# BOOT_SET.net
KiCad netlist of a schematic drawn in Altium Designer
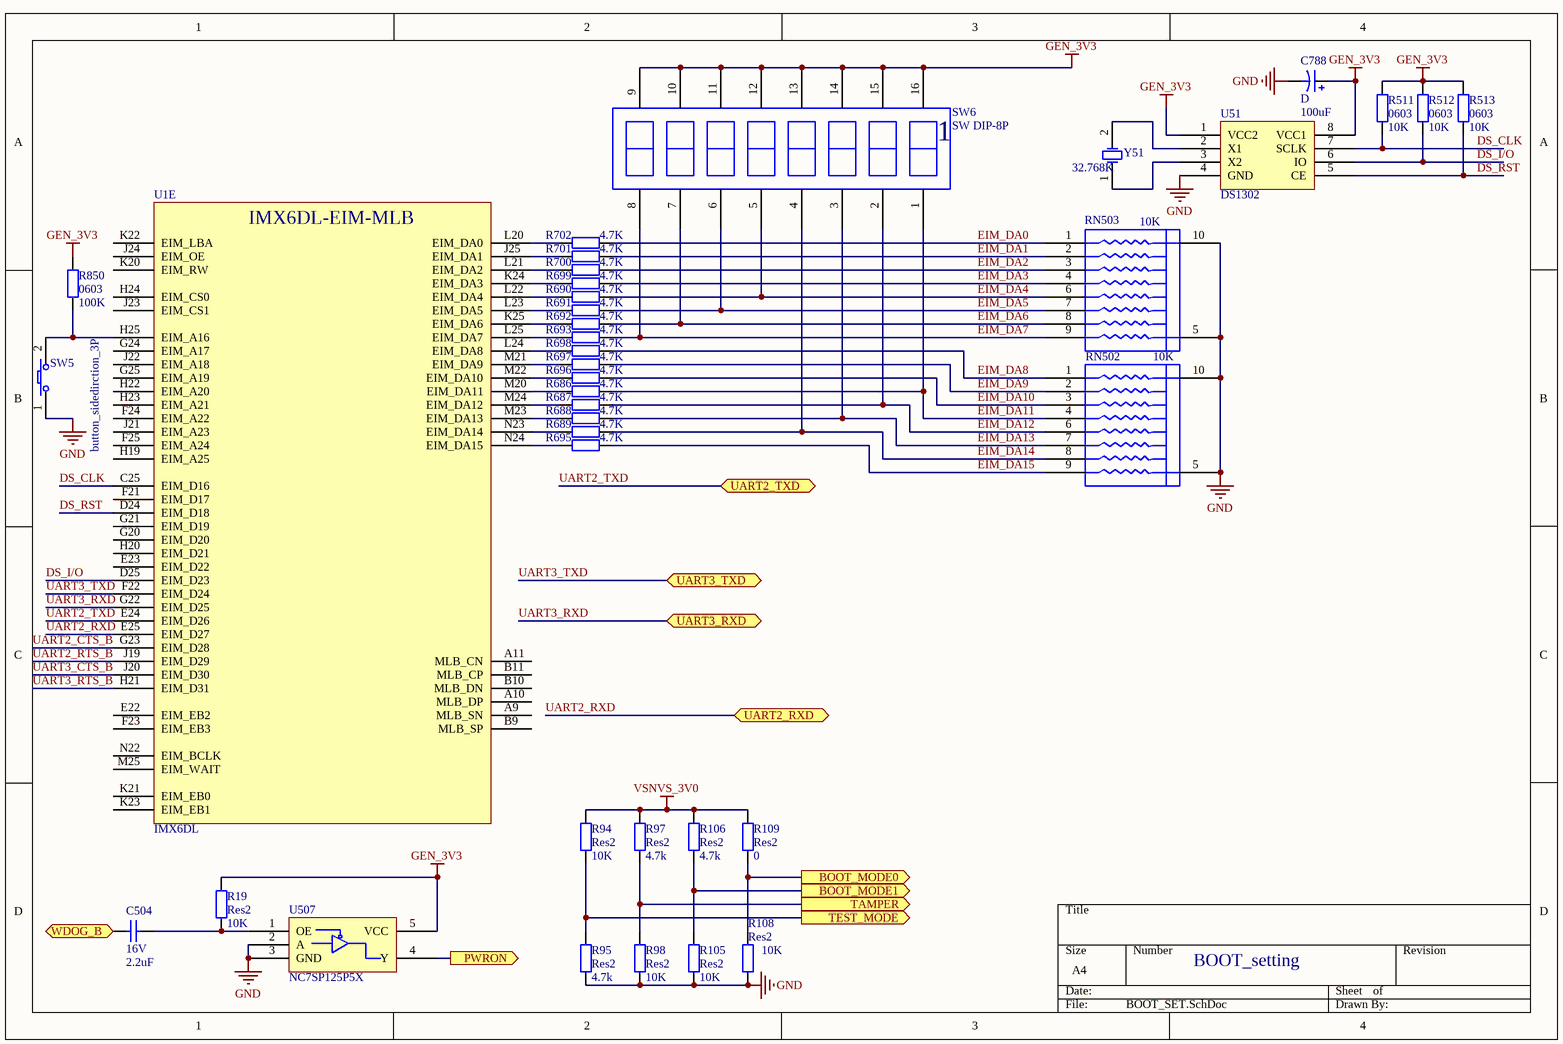
[diagram p0: BOOT_SET.SchDoc]

(export (version "E")
  (design (tool "Eeschema 10.0.6"))
  (components
    (comp (ref "C504")
      (value "16V")
      (footprint "0603")
      (description "Capacitor")
      (fields (field (name "ALTIUM_VALUE") "2.2uF") (field (name "PUBLISHER") "Altium Limited"))
      (libsource (lib "Miscellaneous Devices") (part "Cap"))
    )
    (comp (ref "C788")
      (value "D")
      (footprint "D")
      (description "Polarized Capacitor (Radial)")
      (fields (field (name "ALTIUM_VALUE") "100uF") (field (name "PUBLISHER") "Altium Limited"))
      (libsource (lib "Miscellaneous Devices") (part "Cap Pol1"))
    )
    (comp (ref "R19")
      (value "Res2")
      (footprint "0402")
      (description "Resistor")
      (fields (field (name "ALTIUM_VALUE") "10K") (field (name "PUBLISHER") "Altium Limited"))
      (libsource (lib "") (part "Res2_1"))
    )
    (comp (ref "R94")
      (value "Res2")
      (footprint "0402")
      (description "Resistor")
      (fields (field (name "ALTIUM_VALUE") "10K") (field (name "PUBLISHER") "Altium Limited"))
      (libsource (lib "") (part "Res2_1"))
    )
    (comp (ref "R95")
      (value "Res2")
      (footprint "0402")
      (description "Resistor")
      (fields (field (name "ALTIUM_VALUE") "4.7k") (field (name "PUBLISHER") "Altium Limited"))
      (libsource (lib "") (part "Res2_1"))
    )
    (comp (ref "R97")
      (value "Res2")
      (footprint "0402")
      (description "Resistor")
      (fields (field (name "ALTIUM_VALUE") "4.7k") (field (name "PUBLISHER") "Altium Limited"))
      (libsource (lib "") (part "Res2_1"))
    )
    (comp (ref "R98")
      (value "Res2")
      (footprint "0402")
      (description "Resistor")
      (fields (field (name "ALTIUM_VALUE") "10K") (field (name "PUBLISHER") "Altium Limited"))
      (libsource (lib "") (part "Res2_1"))
    )
    (comp (ref "R105")
      (value "Res2")
      (footprint "0402")
      (description "Resistor")
      (fields (field (name "ALTIUM_VALUE") "10K") (field (name "PUBLISHER") "Altium Limited"))
      (libsource (lib "") (part "Res2_1"))
    )
    (comp (ref "R106")
      (value "Res2")
      (footprint "0402")
      (description "Resistor")
      (fields (field (name "ALTIUM_VALUE") "4.7k") (field (name "PUBLISHER") "Altium Limited"))
      (libsource (lib "") (part "Res2_1"))
    )
    (comp (ref "R108")
      (value "Res2")
      (footprint "0402")
      (description "Resistor")
      (fields (field (name "ALTIUM_VALUE") "10K") (field (name "PUBLISHER") "Altium Limited"))
      (libsource (lib "") (part "Res2_1"))
    )
    (comp (ref "R109")
      (value "Res2")
      (footprint "0402")
      (description "Resistor")
      (fields (field (name "ALTIUM_VALUE") "0") (field (name "PUBLISHER") "Altium Limited"))
      (libsource (lib "") (part "Res2_1"))
    )
    (comp (ref "R511")
      (value "0603")
      (footprint "0603")
      (description "Resistor")
      (fields (field (name "ALTIUM_VALUE") "10K") (field (name "PUBLISHER") "Altium Limited"))
      (libsource (lib "") (part "Res2_1"))
    )
    (comp (ref "R512")
      (value "0603")
      (footprint "0603")
      (description "Resistor")
      (fields (field (name "ALTIUM_VALUE") "10K") (field (name "PUBLISHER") "Altium Limited"))
      (libsource (lib "") (part "Res2_1"))
    )
    (comp (ref "R513")
      (value "0603")
      (footprint "0603")
      (description "Resistor")
      (fields (field (name "ALTIUM_VALUE") "10K") (field (name "PUBLISHER") "Altium Limited"))
      (libsource (lib "") (part "Res2_1"))
    )
    (comp (ref "R686")
      (value "4.7K")
      (footprint "0402")
      (description "Resistor")
      (fields (field (name "Comment") "Res2") (field (name "PUBLISHER") "Altium Limited"))
      (libsource (lib "Miscellaneous Devices") (part "Res2"))
    )
    (comp (ref "R687")
      (value "4.7K")
      (footprint "0402")
      (description "Resistor")
      (fields (field (name "Comment") "Res2") (field (name "PUBLISHER") "Altium Limited"))
      (libsource (lib "Miscellaneous Devices") (part "Res2"))
    )
    (comp (ref "R688")
      (value "4.7K")
      (footprint "0402")
      (description "Resistor")
      (fields (field (name "Comment") "Res2") (field (name "PUBLISHER") "Altium Limited"))
      (libsource (lib "Miscellaneous Devices") (part "Res2"))
    )
    (comp (ref "R689")
      (value "4.7K")
      (footprint "0402")
      (description "Resistor")
      (fields (field (name "Comment") "Res2") (field (name "PUBLISHER") "Altium Limited"))
      (libsource (lib "Miscellaneous Devices") (part "Res2"))
    )
    (comp (ref "R690")
      (value "4.7K")
      (footprint "0402")
      (description "Resistor")
      (fields (field (name "Comment") "Res2") (field (name "PUBLISHER") "Altium Limited"))
      (libsource (lib "Miscellaneous Devices") (part "Res2"))
    )
    (comp (ref "R691")
      (value "4.7K")
      (footprint "0402")
      (description "Resistor")
      (fields (field (name "Comment") "Res2") (field (name "PUBLISHER") "Altium Limited"))
      (libsource (lib "Miscellaneous Devices") (part "Res2"))
    )
    (comp (ref "R692")
      (value "4.7K")
      (footprint "0402")
      (description "Resistor")
      (fields (field (name "Comment") "Res2") (field (name "PUBLISHER") "Altium Limited"))
      (libsource (lib "Miscellaneous Devices") (part "Res2"))
    )
    (comp (ref "R693")
      (value "4.7K")
      (footprint "0402")
      (description "Resistor")
      (fields (field (name "Comment") "Res2") (field (name "PUBLISHER") "Altium Limited"))
      (libsource (lib "Miscellaneous Devices") (part "Res2"))
    )
    (comp (ref "R695")
      (value "4.7K")
      (footprint "0402")
      (description "Resistor")
      (fields (field (name "Comment") "Res2") (field (name "PUBLISHER") "Altium Limited"))
      (libsource (lib "Miscellaneous Devices") (part "Res2"))
    )
    (comp (ref "R696")
      (value "4.7K")
      (footprint "0402")
      (description "Resistor")
      (fields (field (name "Comment") "Res2") (field (name "PUBLISHER") "Altium Limited"))
      (libsource (lib "Miscellaneous Devices") (part "Res2"))
    )
    (comp (ref "R697")
      (value "4.7K")
      (footprint "0402")
      (description "Resistor")
      (fields (field (name "Comment") "Res2") (field (name "PUBLISHER") "Altium Limited"))
      (libsource (lib "Miscellaneous Devices") (part "Res2"))
    )
    (comp (ref "R698")
      (value "4.7K")
      (footprint "0402")
      (description "Resistor")
      (fields (field (name "Comment") "Res2") (field (name "PUBLISHER") "Altium Limited"))
      (libsource (lib "Miscellaneous Devices") (part "Res2"))
    )
    (comp (ref "R699")
      (value "4.7K")
      (footprint "0402")
      (description "Resistor")
      (fields (field (name "Comment") "Res2") (field (name "PUBLISHER") "Altium Limited"))
      (libsource (lib "Miscellaneous Devices") (part "Res2"))
    )
    (comp (ref "R700")
      (value "4.7K")
      (footprint "0402")
      (description "Resistor")
      (fields (field (name "Comment") "Res2") (field (name "PUBLISHER") "Altium Limited"))
      (libsource (lib "Miscellaneous Devices") (part "Res2"))
    )
    (comp (ref "R701")
      (value "4.7K")
      (footprint "0402")
      (description "Resistor")
      (fields (field (name "Comment") "Res2") (field (name "PUBLISHER") "Altium Limited"))
      (libsource (lib "Miscellaneous Devices") (part "Res2"))
    )
    (comp (ref "R702")
      (value "4.7K")
      (footprint "0402")
      (description "Resistor")
      (fields (field (name "Comment") "Res2") (field (name "PUBLISHER") "Altium Limited"))
      (libsource (lib "Miscellaneous Devices") (part "Res2"))
    )
    (comp (ref "R850")
      (value "0603")
      (footprint "0603")
      (description "Resistor")
      (fields (field (name "ALTIUM_VALUE") "100K") (field (name "PUBLISHER") "Altium Limited"))
      (libsource (lib "") (part "Res2_1"))
    )
    (comp (ref "RN502")
      (value "10K")
      (footprint "RN_resistance -SMT8")
      (libsource (lib "IMX6DL") (part "RN res"))
    )
    (comp (ref "RN503")
      (value "10K")
      (footprint "RN_resistance -SMT8")
      (libsource (lib "IMX6DL") (part "RN res"))
    )
    (comp (ref "SW5")
      (value "button_sidedirction_3P")
      (footprint "button_sidedirction_3P 4.5X4.5")
      (libsource (lib "IMX6DL") (part "button_sidedirction_3P"))
    )
    (comp (ref "SW6")
      (value "SW DIP-8P")
      (footprint "dial switch -SMT DIP8")
      (libsource (lib "IMX6DL") (part "SW-8P"))
    )
    (comp (ref "U1")
      (value "IMX6DL")
      (footprint "IMX6DL-BGA624x25")
      (libsource (lib "IMX6DL") (part "IMX6DL"))
    )
    (comp (ref "U51") (value "DS1302") (footprint "DS1302-DIP8") (libsource (lib "IMX6DL") (part "DS1302")))
    (comp (ref "U507")
      (value "NC7SP125P5X")
      (footprint "NC7SP125P5X")
      (libsource (lib "IMX6DL") (part "NC7SP125P5X"))
    )
    (comp (ref "Y51")
      (value "32.768K")
      (footprint "BCY-W2/D3.1")
      (description "Crystal Oscillator")
      (fields (field (name "PUBLISHER") "Altium Limited"))
      (libsource (lib "Miscellaneous Devices") (part "XTAL"))
    )
  )
  (nets
    (net (code "1") (name "/BOOT_MODE0") (class "Default")
      (node (ref "R108") (pin "2") (pinfunction "2_2") (pintype "passive"))
      (node (ref "R109") (pin "1") (pinfunction "1_1") (pintype "passive"))
    )
    (net (code "2") (name "/BOOT_MODE1") (class "Default")
      (node (ref "R105") (pin "2") (pinfunction "2_2") (pintype "passive"))
      (node (ref "R106") (pin "1") (pinfunction "1_1") (pintype "passive"))
    )
    (net (code "3") (name "/DS_CLK") (class "Default")
      (node (ref "R511") (pin "1") (pinfunction "1_1") (pintype "passive"))
      (node (ref "U1") (pin "C25") (pinfunction "EIM_D16_C25") (pintype "passive"))
      (node (ref "U51") (pin "7") (pinfunction "SCLK_7") (pintype "passive"))
    )
    (net (code "4") (name "/DS_I{slash}O") (class "Default")
      (node (ref "R512") (pin "1") (pinfunction "1_1") (pintype "passive"))
      (node (ref "U1") (pin "D25") (pinfunction "EIM_D23_D25") (pintype "passive"))
      (node (ref "U51") (pin "6") (pinfunction "IO_6") (pintype "passive"))
    )
    (net (code "5") (name "/DS_RST") (class "Default")
      (node (ref "R513") (pin "1") (pinfunction "1_1") (pintype "passive"))
      (node (ref "U1") (pin "D24") (pinfunction "EIM_D18_D24") (pintype "passive"))
      (node (ref "U51") (pin "5") (pinfunction "CE_5") (pintype "passive"))
    )
    (net (code "6") (name "/EIM_DA0") (class "Default")
      (node (ref "R702") (pin "2") (pinfunction "2_2") (pintype "passive"))
      (node (ref "RN503") (pin "1") (pinfunction "19_1") (pintype "passive"))
    )
    (net (code "7") (name "/EIM_DA1") (class "Default")
      (node (ref "R701") (pin "2") (pinfunction "2_2") (pintype "passive"))
      (node (ref "RN503") (pin "2") (pinfunction "20_2") (pintype "passive"))
    )
    (net (code "8") (name "/EIM_DA2") (class "Default")
      (node (ref "R700") (pin "2") (pinfunction "2_2") (pintype "passive"))
      (node (ref "RN503") (pin "3") (pinfunction "21_3") (pintype "passive"))
    )
    (net (code "9") (name "/EIM_DA3") (class "Default")
      (node (ref "R699") (pin "2") (pinfunction "2_2") (pintype "passive"))
      (node (ref "RN503") (pin "4") (pinfunction "22_4") (pintype "passive"))
    )
    (net (code "10") (name "/EIM_DA4") (class "Default")
      (node (ref "R690") (pin "2") (pinfunction "2_2") (pintype "passive"))
      (node (ref "RN503") (pin "6") (pinfunction "23_6") (pintype "passive"))
      (node (ref "SW6") (pin "5") (pinfunction "VDDUSB_CAP_5") (pintype "passive"))
    )
    (net (code "11") (name "/EIM_DA5") (class "Default")
      (node (ref "R691") (pin "2") (pinfunction "2_2") (pintype "passive"))
      (node (ref "RN503") (pin "7") (pinfunction "24_7") (pintype "passive"))
      (node (ref "SW6") (pin "6") (pinfunction "VDDUSB_CAP_6") (pintype "passive"))
    )
    (net (code "12") (name "/EIM_DA6") (class "Default")
      (node (ref "R692") (pin "2") (pinfunction "2_2") (pintype "passive"))
      (node (ref "RN503") (pin "8") (pinfunction "25_8") (pintype "passive"))
      (node (ref "SW6") (pin "7") (pinfunction "VDDUSB_CAP_7") (pintype "passive"))
    )
    (net (code "13") (name "/EIM_DA7") (class "Default")
      (node (ref "R693") (pin "2") (pinfunction "2_2") (pintype "passive"))
      (node (ref "RN503") (pin "9") (pinfunction "26_9") (pintype "passive"))
      (node (ref "SW6") (pin "8") (pinfunction "VDDUSB_CAP_8") (pintype "passive"))
    )
    (net (code "14") (name "/EIM_DA8") (class "Default")
      (node (ref "R698") (pin "2") (pinfunction "2_2") (pintype "passive"))
      (node (ref "RN502") (pin "1") (pinfunction "19_1") (pintype "passive"))
    )
    (net (code "15") (name "/EIM_DA9") (class "Default")
      (node (ref "R697") (pin "2") (pinfunction "2_2") (pintype "passive"))
      (node (ref "RN502") (pin "2") (pinfunction "20_2") (pintype "passive"))
    )
    (net (code "16") (name "/EIM_DA10") (class "Default")
      (node (ref "R696") (pin "2") (pinfunction "2_2") (pintype "passive"))
      (node (ref "RN502") (pin "3") (pinfunction "21_3") (pintype "passive"))
    )
    (net (code "17") (name "/EIM_DA11") (class "Default")
      (node (ref "R686") (pin "2") (pinfunction "2_2") (pintype "passive"))
      (node (ref "RN502") (pin "4") (pinfunction "22_4") (pintype "passive"))
      (node (ref "SW6") (pin "1") (pinfunction "VDDUSB_CAP_1") (pintype "passive"))
    )
    (net (code "18") (name "/EIM_DA12") (class "Default")
      (node (ref "R687") (pin "2") (pinfunction "2_2") (pintype "passive"))
      (node (ref "RN502") (pin "6") (pinfunction "23_6") (pintype "passive"))
      (node (ref "SW6") (pin "2") (pinfunction "VDDUSB_CAP_2") (pintype "passive"))
    )
    (net (code "19") (name "/EIM_DA13") (class "Default")
      (node (ref "R688") (pin "2") (pinfunction "2_2") (pintype "passive"))
      (node (ref "RN502") (pin "7") (pinfunction "24_7") (pintype "passive"))
      (node (ref "SW6") (pin "3") (pinfunction "VDDUSB_CAP_3") (pintype "passive"))
    )
    (net (code "20") (name "/EIM_DA14") (class "Default")
      (node (ref "R689") (pin "2") (pinfunction "2_2") (pintype "passive"))
      (node (ref "RN502") (pin "8") (pinfunction "25_8") (pintype "passive"))
      (node (ref "SW6") (pin "4") (pinfunction "VDDUSB_CAP_4") (pintype "passive"))
    )
    (net (code "21") (name "/EIM_DA15") (class "Default")
      (node (ref "R695") (pin "2") (pinfunction "2_2") (pintype "passive"))
      (node (ref "RN502") (pin "9") (pinfunction "26_9") (pintype "passive"))
    )
    (net (code "22") (name "/PWRON") (class "Default")
      (node (ref "U507") (pin "4") (pinfunction "Y_4") (pintype "passive"))
    )
    (net (code "23") (name "/TAMPER") (class "Default")
      (node (ref "R97") (pin "1") (pinfunction "1_1") (pintype "passive"))
      (node (ref "R98") (pin "2") (pinfunction "2_2") (pintype "passive"))
    )
    (net (code "24") (name "/TEST_MODE") (class "Default")
      (node (ref "R94") (pin "1") (pinfunction "1_1") (pintype "passive"))
      (node (ref "R95") (pin "2") (pinfunction "2_2") (pintype "passive"))
    )
    (net (code "25") (name "/UART2_CTS_B") (class "Default")
      (node (ref "U1") (pin "G23") (pinfunction "EIM_D28_G23") (pintype "passive"))
    )
    (net (code "26") (name "/UART2_RTS_B") (class "Default")
      (node (ref "U1") (pin "J19") (pinfunction "EIM_D29_J19") (pintype "passive"))
    )
    (net (code "27") (name "/UART2_RXD") (class "Default")
      (node (ref "U1") (pin "E25") (pinfunction "EIM_D27_E25") (pintype "passive"))
    )
    (net (code "28") (name "/UART2_TXD") (class "Default")
      (node (ref "U1") (pin "E24") (pinfunction "EIM_D26_E24") (pintype "passive"))
    )
    (net (code "29") (name "/UART3_CTS_B") (class "Default")
      (node (ref "U1") (pin "J20") (pinfunction "EIM_D30_J20") (pintype "passive"))
    )
    (net (code "30") (name "/UART3_RTS_B") (class "Default")
      (node (ref "U1") (pin "H21") (pinfunction "EIM_D31_H21") (pintype "passive"))
    )
    (net (code "31") (name "/UART3_RXD") (class "Default")
      (node (ref "U1") (pin "G22") (pinfunction "EIM_D25_G22") (pintype "passive"))
    )
    (net (code "32") (name "/UART3_TXD") (class "Default")
      (node (ref "U1") (pin "F22") (pinfunction "EIM_D24_F22") (pintype "passive"))
    )
    (net (code "33") (name "/WDOG_B") (class "Default")
      (node (ref "C504") (pin "1") (pinfunction "1_1") (pintype "passive"))
    )
    (net (code "34") (name "GEN_3V3") (class "Default")
      (node (ref "C788") (pin "1") (pinfunction "1_1") (pintype "passive"))
      (node (ref "R19") (pin "2") (pinfunction "2_2") (pintype "passive"))
      (node (ref "R511") (pin "2") (pinfunction "2_2") (pintype "passive"))
      (node (ref "R512") (pin "2") (pinfunction "2_2") (pintype "passive"))
      (node (ref "R513") (pin "2") (pinfunction "2_2") (pintype "passive"))
      (node (ref "R850") (pin "2") (pinfunction "2_2") (pintype "passive"))
      (node (ref "SW6") (pin "10") (pinfunction "10_10") (pintype "passive"))
      (node (ref "SW6") (pin "11") (pinfunction "11_11") (pintype "passive"))
      (node (ref "SW6") (pin "12") (pinfunction "12_12") (pintype "passive"))
      (node (ref "SW6") (pin "13") (pinfunction "13_13") (pintype "passive"))
      (node (ref "SW6") (pin "14") (pinfunction "14_14") (pintype "passive"))
      (node (ref "SW6") (pin "15") (pinfunction "15_15") (pintype "passive"))
      (node (ref "SW6") (pin "16") (pinfunction "16_16") (pintype "passive"))
      (node (ref "SW6") (pin "9") (pinfunction "9_9") (pintype "passive"))
      (node (ref "U507") (pin "5") (pinfunction "VCC_5") (pintype "passive"))
      (node (ref "U51") (pin "1") (pinfunction "VCC2_1") (pintype "passive"))
      (node (ref "U51") (pin "8") (pinfunction "VCC1_8") (pintype "passive"))
    )
    (net (code "35") (name "GND") (class "Default")
      (node (ref "C788") (pin "2") (pinfunction "2_2") (pintype "passive"))
      (node (ref "R105") (pin "1") (pinfunction "1_1") (pintype "passive"))
      (node (ref "R108") (pin "1") (pinfunction "1_1") (pintype "passive"))
      (node (ref "R95") (pin "1") (pinfunction "1_1") (pintype "passive"))
      (node (ref "R98") (pin "1") (pinfunction "1_1") (pintype "passive"))
      (node (ref "RN502") (pin "10") (pinfunction "18_10") (pintype "passive"))
      (node (ref "RN502") (pin "5") (pinfunction "17_5") (pintype "passive"))
      (node (ref "RN503") (pin "10") (pinfunction "18_10") (pintype "passive"))
      (node (ref "RN503") (pin "5") (pinfunction "17_5") (pintype "passive"))
      (node (ref "SW5") (pin "1") (pinfunction "3_1") (pintype "passive"))
      (node (ref "U507") (pin "2") (pinfunction "A_2") (pintype "passive"))
      (node (ref "U507") (pin "3") (pinfunction "GND_3") (pintype "passive"))
      (node (ref "U51") (pin "4") (pinfunction "GND_4") (pintype "passive"))
    )
    (net (code "36") (name "Net-(U1E-EIM_A16)") (class "Default")
      (node (ref "R850") (pin "1") (pinfunction "1_1") (pintype "passive"))
      (node (ref "SW5") (pin "2") (pinfunction "2_2") (pintype "passive"))
      (node (ref "U1") (pin "H25") (pinfunction "EIM_A16_H25") (pintype "passive"))
    )
    (net (code "37") (name "Net-(U1E-EIM_DA0)") (class "Default")
      (node (ref "R702") (pin "1") (pinfunction "1_1") (pintype "passive"))
      (node (ref "U1") (pin "L20") (pinfunction "EIM_DA0_L20") (pintype "passive"))
    )
    (net (code "38") (name "Net-(U1E-EIM_DA1)") (class "Default")
      (node (ref "R701") (pin "1") (pinfunction "1_1") (pintype "passive"))
      (node (ref "U1") (pin "J25") (pinfunction "EIM_DA1_J25") (pintype "passive"))
    )
    (net (code "39") (name "Net-(U1E-EIM_DA2)") (class "Default")
      (node (ref "R700") (pin "1") (pinfunction "1_1") (pintype "passive"))
      (node (ref "U1") (pin "L21") (pinfunction "EIM_DA2_L21") (pintype "passive"))
    )
    (net (code "40") (name "Net-(U1E-EIM_DA3)") (class "Default")
      (node (ref "R699") (pin "1") (pinfunction "1_1") (pintype "passive"))
      (node (ref "U1") (pin "K24") (pinfunction "EIM_DA3_K24") (pintype "passive"))
    )
    (net (code "41") (name "Net-(U1E-EIM_DA4)") (class "Default")
      (node (ref "R690") (pin "1") (pinfunction "1_1") (pintype "passive"))
      (node (ref "U1") (pin "L22") (pinfunction "EIM_DA4_L22") (pintype "passive"))
    )
    (net (code "42") (name "Net-(U1E-EIM_DA5)") (class "Default")
      (node (ref "R691") (pin "1") (pinfunction "1_1") (pintype "passive"))
      (node (ref "U1") (pin "L23") (pinfunction "EIM_DA5_L23") (pintype "passive"))
    )
    (net (code "43") (name "Net-(U1E-EIM_DA6)") (class "Default")
      (node (ref "R692") (pin "1") (pinfunction "1_1") (pintype "passive"))
      (node (ref "U1") (pin "K25") (pinfunction "EIM_DA6_K25") (pintype "passive"))
    )
    (net (code "44") (name "Net-(U1E-EIM_DA7)") (class "Default")
      (node (ref "R693") (pin "1") (pinfunction "1_1") (pintype "passive"))
      (node (ref "U1") (pin "L25") (pinfunction "EIM_DA7_L25") (pintype "passive"))
    )
    (net (code "45") (name "Net-(U1E-EIM_DA8)") (class "Default")
      (node (ref "R698") (pin "1") (pinfunction "1_1") (pintype "passive"))
      (node (ref "U1") (pin "L24") (pinfunction "EIM_DA8_L24") (pintype "passive"))
    )
    (net (code "46") (name "Net-(U1E-EIM_DA9)") (class "Default")
      (node (ref "R697") (pin "1") (pinfunction "1_1") (pintype "passive"))
      (node (ref "U1") (pin "M21") (pinfunction "EIM_DA9_M21") (pintype "passive"))
    )
    (net (code "47") (name "Net-(U1E-EIM_DA10)") (class "Default")
      (node (ref "R696") (pin "1") (pinfunction "1_1") (pintype "passive"))
      (node (ref "U1") (pin "M22") (pinfunction "EIM_DA10_M22") (pintype "passive"))
    )
    (net (code "48") (name "Net-(U1E-EIM_DA11)") (class "Default")
      (node (ref "R686") (pin "1") (pinfunction "1_1") (pintype "passive"))
      (node (ref "U1") (pin "M20") (pinfunction "EIM_DA11_M20") (pintype "passive"))
    )
    (net (code "49") (name "Net-(U1E-EIM_DA12)") (class "Default")
      (node (ref "R687") (pin "1") (pinfunction "1_1") (pintype "passive"))
      (node (ref "U1") (pin "M24") (pinfunction "EIM_DA12_M24") (pintype "passive"))
    )
    (net (code "50") (name "Net-(U1E-EIM_DA13)") (class "Default")
      (node (ref "R688") (pin "1") (pinfunction "1_1") (pintype "passive"))
      (node (ref "U1") (pin "M23") (pinfunction "EIM_DA13_M23") (pintype "passive"))
    )
    (net (code "51") (name "Net-(U1E-EIM_DA14)") (class "Default")
      (node (ref "R689") (pin "1") (pinfunction "1_1") (pintype "passive"))
      (node (ref "U1") (pin "N23") (pinfunction "EIM_DA14_N23") (pintype "passive"))
    )
    (net (code "52") (name "Net-(U1E-EIM_DA15)") (class "Default")
      (node (ref "R695") (pin "1") (pinfunction "1_1") (pintype "passive"))
      (node (ref "U1") (pin "N24") (pinfunction "EIM_DA15_N24") (pintype "passive"))
    )
    (net (code "53") (name "Net-(U51-X1)") (class "Default")
      (node (ref "U51") (pin "2") (pinfunction "X1_2") (pintype "passive"))
      (node (ref "Y51") (pin "2") (pinfunction "OSC2_2") (pintype "passive"))
    )
    (net (code "54") (name "Net-(U51-X2)") (class "Default")
      (node (ref "U51") (pin "3") (pinfunction "X2_3") (pintype "passive"))
      (node (ref "Y51") (pin "1") (pinfunction "OSC1_1") (pintype "passive"))
    )
    (net (code "55") (name "Net-(U507-OE)") (class "Default")
      (node (ref "C504") (pin "2") (pinfunction "2_2") (pintype "passive"))
      (node (ref "R19") (pin "1") (pinfunction "1_1") (pintype "passive"))
      (node (ref "U507") (pin "1") (pinfunction "OE_1") (pintype "passive"))
    )
    (net (code "56") (name "VSNVS_3V0") (class "Default")
      (node (ref "R106") (pin "2") (pinfunction "2_2") (pintype "passive"))
      (node (ref "R109") (pin "2") (pinfunction "2_2") (pintype "passive"))
      (node (ref "R94") (pin "2") (pinfunction "2_2") (pintype "passive"))
      (node (ref "R97") (pin "2") (pinfunction "2_2") (pintype "passive"))
    )
    (net (code "57") (name "unconnected-(U1E-EIM_A17-PadG24)") (class "Default")
      (node (ref "U1") (pin "G24") (pinfunction "EIM_A17_G24") (pintype "passive"))
    )
    (net (code "58") (name "unconnected-(U1E-EIM_A18-PadJ22)") (class "Default")
      (node (ref "U1") (pin "J22") (pinfunction "EIM_A18_J22") (pintype "passive"))
    )
    (net (code "59") (name "unconnected-(U1E-EIM_A19-PadG25)") (class "Default")
      (node (ref "U1") (pin "G25") (pinfunction "EIM_A19_G25") (pintype "passive"))
    )
    (net (code "60") (name "unconnected-(U1E-EIM_A20-PadH22)") (class "Default")
      (node (ref "U1") (pin "H22") (pinfunction "EIM_A20_H22") (pintype "passive"))
    )
    (net (code "61") (name "unconnected-(U1E-EIM_A21-PadH23)") (class "Default")
      (node (ref "U1") (pin "H23") (pinfunction "EIM_A21_H23") (pintype "passive"))
    )
    (net (code "62") (name "unconnected-(U1E-EIM_A22-PadF24)") (class "Default")
      (node (ref "U1") (pin "F24") (pinfunction "EIM_A22_F24") (pintype "passive"))
    )
    (net (code "63") (name "unconnected-(U1E-EIM_A23-PadJ21)") (class "Default")
      (node (ref "U1") (pin "J21") (pinfunction "EIM_A23_J21") (pintype "passive"))
    )
    (net (code "64") (name "unconnected-(U1E-EIM_A24-PadF25)") (class "Default")
      (node (ref "U1") (pin "F25") (pinfunction "EIM_A24_F25") (pintype "passive"))
    )
    (net (code "65") (name "unconnected-(U1E-EIM_A25-PadH19)") (class "Default")
      (node (ref "U1") (pin "H19") (pinfunction "EIM_A25_H19") (pintype "passive"))
    )
    (net (code "66") (name "unconnected-(U1E-EIM_BCLK-PadN22)") (class "Default")
      (node (ref "U1") (pin "N22") (pinfunction "EIM_BCLK_N22") (pintype "passive"))
    )
    (net (code "67") (name "unconnected-(U1E-EIM_CS0-PadH24)") (class "Default")
      (node (ref "U1") (pin "H24") (pinfunction "EIM_CS0_H24") (pintype "passive"))
    )
    (net (code "68") (name "unconnected-(U1E-EIM_CS1-PadJ23)") (class "Default")
      (node (ref "U1") (pin "J23") (pinfunction "EIM_CS1_J23") (pintype "passive"))
    )
    (net (code "69") (name "unconnected-(U1E-EIM_D17-PadF21)") (class "Default")
      (node (ref "U1") (pin "F21") (pinfunction "EIM_D17_F21") (pintype "passive"))
    )
    (net (code "70") (name "unconnected-(U1E-EIM_D19-PadG21)") (class "Default")
      (node (ref "U1") (pin "G21") (pinfunction "EIM_D19_G21") (pintype "passive"))
    )
    (net (code "71") (name "unconnected-(U1E-EIM_D20-PadG20)") (class "Default")
      (node (ref "U1") (pin "G20") (pinfunction "EIM_D20_G20") (pintype "passive"))
    )
    (net (code "72") (name "unconnected-(U1E-EIM_D21-PadH20)") (class "Default")
      (node (ref "U1") (pin "H20") (pinfunction "EIM_D21_H20") (pintype "passive"))
    )
    (net (code "73") (name "unconnected-(U1E-EIM_D22-PadE23)") (class "Default")
      (node (ref "U1") (pin "E23") (pinfunction "EIM_D22_E23") (pintype "passive"))
    )
    (net (code "74") (name "unconnected-(U1E-EIM_EB0-PadK21)") (class "Default")
      (node (ref "U1") (pin "K21") (pinfunction "EIM_EB0_K21") (pintype "passive"))
    )
    (net (code "75") (name "unconnected-(U1E-EIM_EB1-PadK23)") (class "Default")
      (node (ref "U1") (pin "K23") (pinfunction "EIM_EB1_K23") (pintype "passive"))
    )
    (net (code "76") (name "unconnected-(U1E-EIM_EB2-PadE22)") (class "Default")
      (node (ref "U1") (pin "E22") (pinfunction "EIM_EB2_E22") (pintype "passive"))
    )
    (net (code "77") (name "unconnected-(U1E-EIM_EB3-PadF23)") (class "Default")
      (node (ref "U1") (pin "F23") (pinfunction "EIM_EB3_F23") (pintype "passive"))
    )
    (net (code "78") (name "unconnected-(U1E-EIM_LBA-PadK22)") (class "Default")
      (node (ref "U1") (pin "K22") (pinfunction "EIM_LBA_K22") (pintype "passive"))
    )
    (net (code "79") (name "unconnected-(U1E-EIM_OE-PadJ24)") (class "Default")
      (node (ref "U1") (pin "J24") (pinfunction "EIM_OE_J24") (pintype "passive"))
    )
    (net (code "80") (name "unconnected-(U1E-EIM_RW-PadK20)") (class "Default")
      (node (ref "U1") (pin "K20") (pinfunction "EIM_RW_K20") (pintype "passive"))
    )
    (net (code "81") (name "unconnected-(U1E-EIM_WAIT-PadM25)") (class "Default")
      (node (ref "U1") (pin "M25") (pinfunction "EIM_WAIT_M25") (pintype "passive"))
    )
    (net (code "82") (name "unconnected-(U1E-MLB_CN-PadA11)") (class "Default")
      (node (ref "U1") (pin "A11") (pinfunction "MLB_CN_A11") (pintype "passive"))
    )
    (net (code "83") (name "unconnected-(U1E-MLB_CP-PadB11)") (class "Default")
      (node (ref "U1") (pin "B11") (pinfunction "MLB_CP_B11") (pintype "passive"))
    )
    (net (code "84") (name "unconnected-(U1E-MLB_DN-PadB10)") (class "Default")
      (node (ref "U1") (pin "B10") (pinfunction "MLB_DN_B10") (pintype "passive"))
    )
    (net (code "85") (name "unconnected-(U1E-MLB_DP-PadA10)") (class "Default")
      (node (ref "U1") (pin "A10") (pinfunction "MLB_DP_A10") (pintype "passive"))
    )
    (net (code "86") (name "unconnected-(U1E-MLB_SN-PadA9)") (class "Default")
      (node (ref "U1") (pin "A9") (pinfunction "MLB_SN_A9") (pintype "passive"))
    )
    (net (code "87") (name "unconnected-(U1E-MLB_SP-PadB9)") (class "Default")
      (node (ref "U1") (pin "B9") (pinfunction "MLB_SP_B9") (pintype "passive"))
    )
  )
)
